# IN-17_logic_V1_0.net
KiCad netlist of a schematic drawn in EAGLE
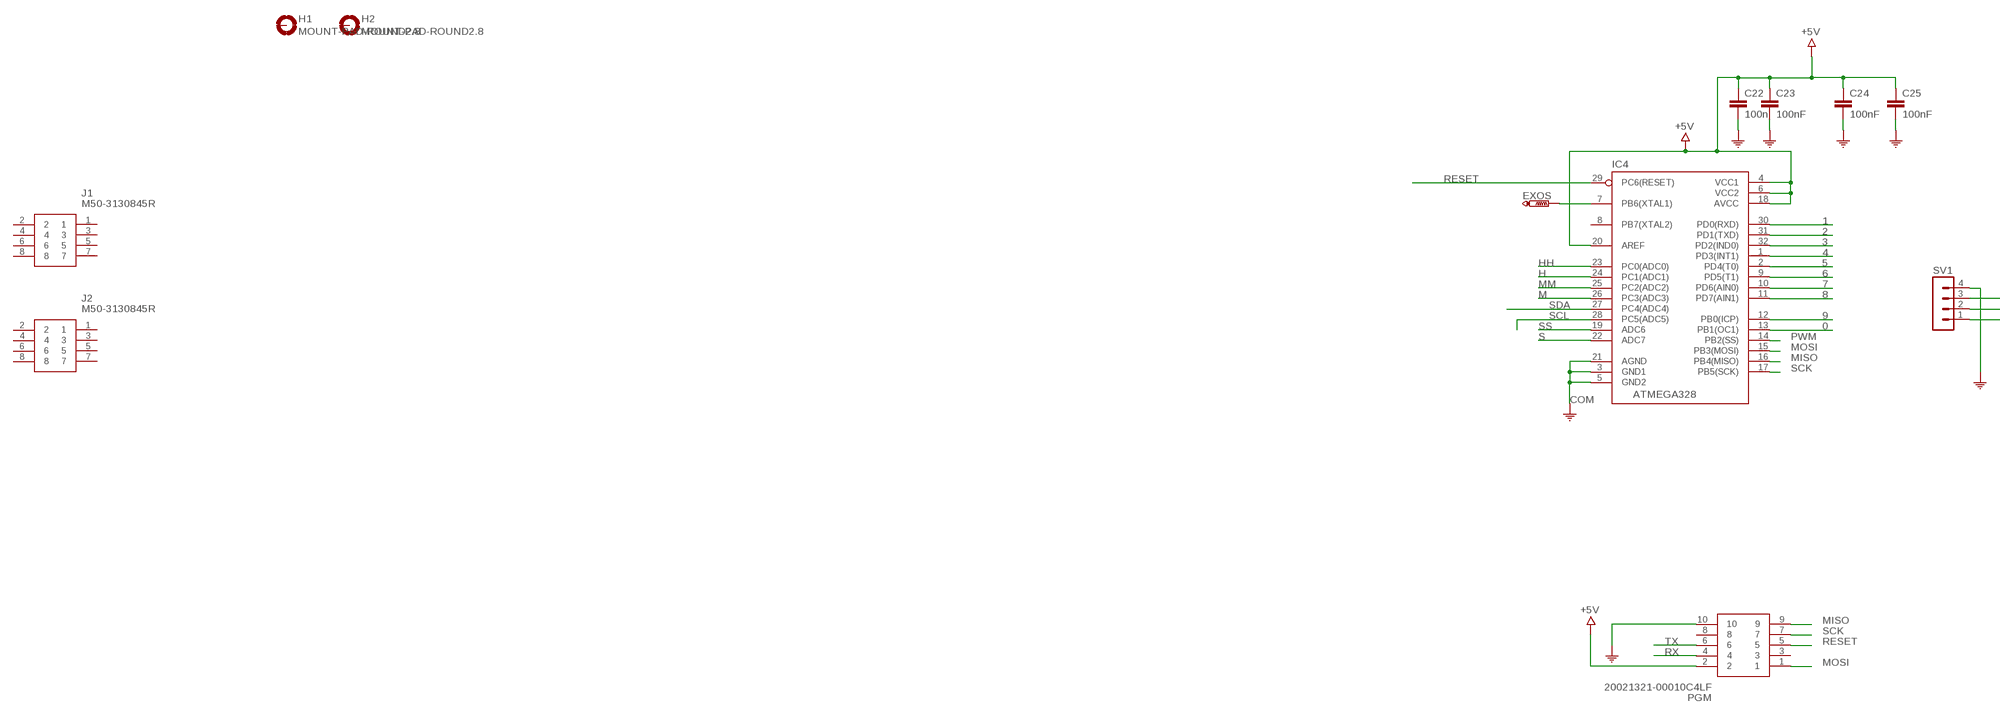
[diagram p0: schematic, sheet 1, part 1 of 2]
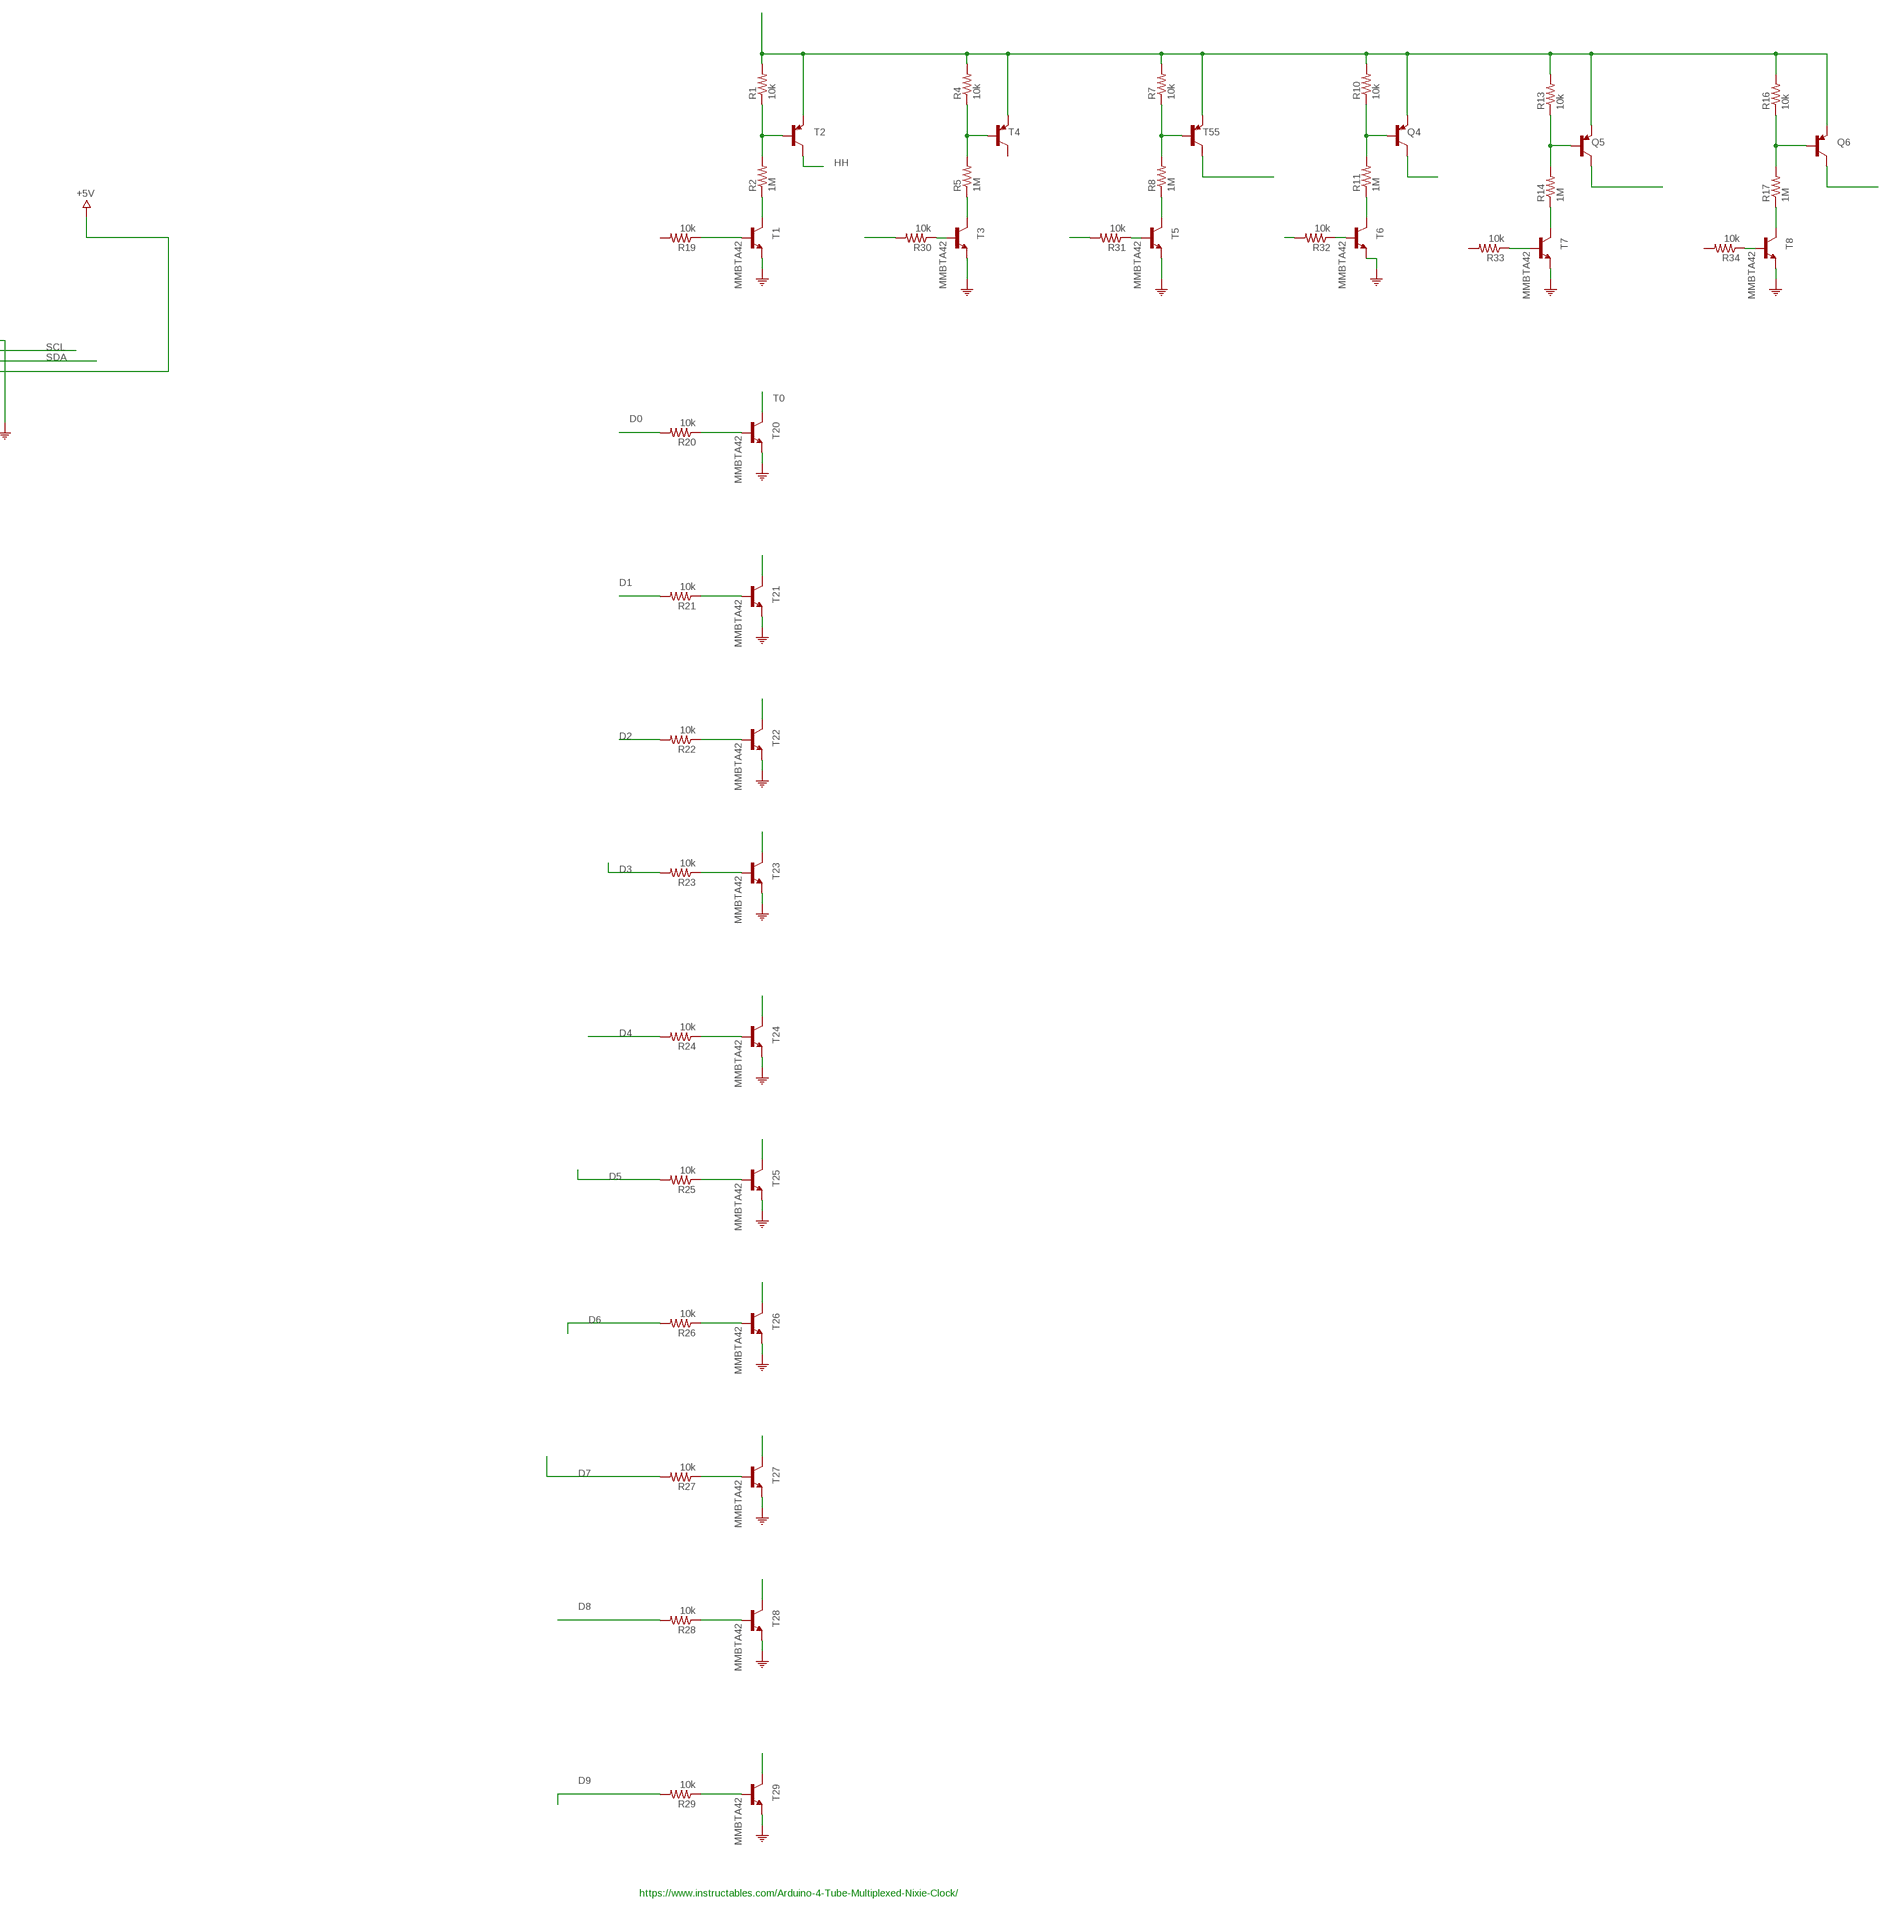
[diagram p1: schematic, sheet 1, part 2 of 2]

(export (version "E")
  (design (tool "Eeschema 10.0.6"))
  (components
    (comp (ref "C22")
      (value "100n")
      (footprint "eagle-import:C0805")
      (libsource (lib "eagle-import") (part "C-EUC0805"))
    )
    (comp (ref "C23")
      (value "100nF")
      (footprint "eagle-import:C0805")
      (libsource (lib "eagle-import") (part "C-EUC0805"))
    )
    (comp (ref "C24")
      (value "100nF")
      (footprint "eagle-import:C0805")
      (libsource (lib "eagle-import") (part "C-EUC0805"))
    )
    (comp (ref "C25")
      (value "100nF")
      (footprint "eagle-import:C0805")
      (libsource (lib "eagle-import") (part "C-EUC0805"))
    )
    (comp (ref "EXOS")
      (value "PTR1TP09R")
      (footprint "eagle-import:TP09R")
      (libsource (lib "eagle-import") (part "PTR1TP09R"))
    )
    (comp (ref "H1")
      (value "MOUNT-PAD-ROUND2.8")
      (footprint "eagle-import:2,8-PAD")
      (libsource (lib "eagle-import") (part "MOUNT-PAD-ROUND2.8"))
    )
    (comp (ref "H2")
      (value "MOUNT-PAD-ROUND2.8")
      (footprint "eagle-import:2,8-PAD")
      (libsource (lib "eagle-import") (part "MOUNT-PAD-ROUND2.8"))
    )
    (comp (ref "IC4")
      (value "ATMEGA328")
      (footprint "eagle-import:QFP032")
      (libsource (lib "eagle-import") (part "ATMEGA168-20AU"))
    )
    (comp (ref "J1")
      (value "M50-3130845R")
      (footprint "eagle-import:M503130845R")
      (fields (field (name "MOUSER_PART_NUMBER") "855-M50-3130845R"))
      (libsource (lib "eagle-import") (part "M50-3130845R"))
    )
    (comp (ref "J2")
      (value "M50-3130845R")
      (footprint "eagle-import:M503130845R")
      (fields (field (name "MOUSER_PART_NUMBER") "855-M50-3130845R"))
      (libsource (lib "eagle-import") (part "M50-3130845R"))
    )
    (comp (ref "PGM")
      (value "20021321-00010C4LF")
      (footprint "eagle-import:2002132100010C4LF")
      (fields (field (name "MOUSER_PART_NUMBER") "649-202132100010C4LF"))
      (libsource (lib "eagle-import") (part "20021321-00010C4LF"))
    )
    (comp (ref "Q4")
      (value "TRANSISTOR_BJT_PNP-SOT-23-BCE")
      (footprint "eagle-import:SOT-23")
      (libsource (lib "eagle-import") (part "TRANSISTOR_BJT_PNP-SOT-23-BCE"))
    )
    (comp (ref "Q5")
      (value "TRANSISTOR_BJT_PNP-SOT-23-BCE")
      (footprint "eagle-import:SOT-23")
      (libsource (lib "eagle-import") (part "TRANSISTOR_BJT_PNP-SOT-23-BCE"))
    )
    (comp (ref "Q6")
      (value "TRANSISTOR_BJT_PNP-SOT-23-BCE")
      (footprint "eagle-import:SOT-23")
      (libsource (lib "eagle-import") (part "TRANSISTOR_BJT_PNP-SOT-23-BCE"))
    )
    (comp (ref "R1")
      (value "10k")
      (footprint "eagle-import:R0805")
      (libsource (lib "eagle-import") (part "R-US_R0805"))
    )
    (comp (ref "R2")
      (value "1M")
      (footprint "eagle-import:R0805")
      (libsource (lib "eagle-import") (part "R-US_R0805"))
    )
    (comp (ref "R4")
      (value "10k")
      (footprint "eagle-import:R0805")
      (libsource (lib "eagle-import") (part "R-US_R0805"))
    )
    (comp (ref "R5")
      (value "1M")
      (footprint "eagle-import:R0805")
      (libsource (lib "eagle-import") (part "R-US_R0805"))
    )
    (comp (ref "R7")
      (value "10k")
      (footprint "eagle-import:R0805")
      (libsource (lib "eagle-import") (part "R-US_R0805"))
    )
    (comp (ref "R8")
      (value "1M")
      (footprint "eagle-import:R0805")
      (libsource (lib "eagle-import") (part "R-US_R0805"))
    )
    (comp (ref "R10")
      (value "10k")
      (footprint "eagle-import:R0805")
      (libsource (lib "eagle-import") (part "R-US_R0805"))
    )
    (comp (ref "R11")
      (value "1M")
      (footprint "eagle-import:R0805")
      (libsource (lib "eagle-import") (part "R-US_R0805"))
    )
    (comp (ref "R13")
      (value "10k")
      (footprint "eagle-import:R0805")
      (libsource (lib "eagle-import") (part "R-US_R0805"))
    )
    (comp (ref "R14")
      (value "1M")
      (footprint "eagle-import:R0805")
      (libsource (lib "eagle-import") (part "R-US_R0805"))
    )
    (comp (ref "R16")
      (value "10k")
      (footprint "eagle-import:R0805")
      (libsource (lib "eagle-import") (part "R-US_R0805"))
    )
    (comp (ref "R17")
      (value "1M")
      (footprint "eagle-import:R0805")
      (libsource (lib "eagle-import") (part "R-US_R0805"))
    )
    (comp (ref "R19")
      (value "10k")
      (footprint "eagle-import:R0805")
      (libsource (lib "eagle-import") (part "R-US_R0805"))
    )
    (comp (ref "R20")
      (value "10k")
      (footprint "eagle-import:R0805")
      (libsource (lib "eagle-import") (part "R-US_R0805"))
    )
    (comp (ref "R21")
      (value "10k")
      (footprint "eagle-import:R0805")
      (libsource (lib "eagle-import") (part "R-US_R0805"))
    )
    (comp (ref "R22")
      (value "10k")
      (footprint "eagle-import:R0805")
      (libsource (lib "eagle-import") (part "R-US_R0805"))
    )
    (comp (ref "R23")
      (value "10k")
      (footprint "eagle-import:R0805")
      (libsource (lib "eagle-import") (part "R-US_R0805"))
    )
    (comp (ref "R24")
      (value "10k")
      (footprint "eagle-import:R0805")
      (libsource (lib "eagle-import") (part "R-US_R0805"))
    )
    (comp (ref "R25")
      (value "10k")
      (footprint "eagle-import:R0805")
      (libsource (lib "eagle-import") (part "R-US_R0805"))
    )
    (comp (ref "R26")
      (value "10k")
      (footprint "eagle-import:R0805")
      (libsource (lib "eagle-import") (part "R-US_R0805"))
    )
    (comp (ref "R27")
      (value "10k")
      (footprint "eagle-import:R0805")
      (libsource (lib "eagle-import") (part "R-US_R0805"))
    )
    (comp (ref "R28")
      (value "10k")
      (footprint "eagle-import:R0805")
      (libsource (lib "eagle-import") (part "R-US_R0805"))
    )
    (comp (ref "R29")
      (value "10k")
      (footprint "eagle-import:R0805")
      (libsource (lib "eagle-import") (part "R-US_R0805"))
    )
    (comp (ref "R30")
      (value "10k")
      (footprint "eagle-import:R0805")
      (libsource (lib "eagle-import") (part "R-US_R0805"))
    )
    (comp (ref "R31")
      (value "10k")
      (footprint "eagle-import:R0805")
      (libsource (lib "eagle-import") (part "R-US_R0805"))
    )
    (comp (ref "R32")
      (value "10k")
      (footprint "eagle-import:R0805")
      (libsource (lib "eagle-import") (part "R-US_R0805"))
    )
    (comp (ref "R33")
      (value "10k")
      (footprint "eagle-import:R0805")
      (libsource (lib "eagle-import") (part "R-US_R0805"))
    )
    (comp (ref "R34")
      (value "10k")
      (footprint "eagle-import:R0805")
      (libsource (lib "eagle-import") (part "R-US_R0805"))
    )
    (comp (ref "SV1")
      (value "MA04-1")
      (footprint "eagle-import:MA04-1")
      (libsource (lib "eagle-import") (part "MA04-1"))
    )
    (comp (ref "T1")
      (value "MMBTA42")
      (footprint "eagle-import:SOT23")
      (libsource (lib "eagle-import") (part "BC846"))
    )
    (comp (ref "T2")
      (value "TRANSISTOR_BJT_PNP-SOT-23-BCE")
      (footprint "eagle-import:SOT-23")
      (libsource (lib "eagle-import") (part "TRANSISTOR_BJT_PNP-SOT-23-BCE"))
    )
    (comp (ref "T3")
      (value "MMBTA42")
      (footprint "eagle-import:SOT23")
      (libsource (lib "eagle-import") (part "BC846"))
    )
    (comp (ref "T4")
      (value "TRANSISTOR_BJT_PNP-SOT-23-BCE")
      (footprint "eagle-import:SOT-23")
      (libsource (lib "eagle-import") (part "TRANSISTOR_BJT_PNP-SOT-23-BCE"))
    )
    (comp (ref "T5")
      (value "MMBTA42")
      (footprint "eagle-import:SOT23")
      (libsource (lib "eagle-import") (part "BC846"))
    )
    (comp (ref "T6")
      (value "MMBTA42")
      (footprint "eagle-import:SOT23")
      (libsource (lib "eagle-import") (part "BC846"))
    )
    (comp (ref "T7")
      (value "MMBTA42")
      (footprint "eagle-import:SOT23")
      (libsource (lib "eagle-import") (part "BC846"))
    )
    (comp (ref "T8")
      (value "MMBTA42")
      (footprint "eagle-import:SOT23")
      (libsource (lib "eagle-import") (part "BC846"))
    )
    (comp (ref "T20")
      (value "MMBTA42")
      (footprint "eagle-import:SOT23")
      (libsource (lib "eagle-import") (part "BC846"))
    )
    (comp (ref "T21")
      (value "MMBTA42")
      (footprint "eagle-import:SOT23")
      (libsource (lib "eagle-import") (part "BC846"))
    )
    (comp (ref "T22")
      (value "MMBTA42")
      (footprint "eagle-import:SOT23")
      (libsource (lib "eagle-import") (part "BC846"))
    )
    (comp (ref "T23")
      (value "MMBTA42")
      (footprint "eagle-import:SOT23")
      (libsource (lib "eagle-import") (part "BC846"))
    )
    (comp (ref "T24")
      (value "MMBTA42")
      (footprint "eagle-import:SOT23")
      (libsource (lib "eagle-import") (part "BC846"))
    )
    (comp (ref "T25")
      (value "MMBTA42")
      (footprint "eagle-import:SOT23")
      (libsource (lib "eagle-import") (part "BC846"))
    )
    (comp (ref "T26")
      (value "MMBTA42")
      (footprint "eagle-import:SOT23")
      (libsource (lib "eagle-import") (part "BC846"))
    )
    (comp (ref "T27")
      (value "MMBTA42")
      (footprint "eagle-import:SOT23")
      (libsource (lib "eagle-import") (part "BC846"))
    )
    (comp (ref "T28")
      (value "MMBTA42")
      (footprint "eagle-import:SOT23")
      (libsource (lib "eagle-import") (part "BC846"))
    )
    (comp (ref "T29")
      (value "MMBTA42")
      (footprint "eagle-import:SOT23")
      (libsource (lib "eagle-import") (part "BC846"))
    )
    (comp (ref "T55")
      (value "TRANSISTOR_BJT_PNP-SOT-23-BCE")
      (footprint "eagle-import:SOT-23")
      (libsource (lib "eagle-import") (part "TRANSISTOR_BJT_PNP-SOT-23-BCE"))
    )
  )
  (nets
    (net (code "1") (name "+5V") (class "Default")
      (node (ref "C22") (pin "1") (pinfunction "1_1") (pintype "passive"))
      (node (ref "C23") (pin "1") (pinfunction "1_1") (pintype "passive"))
      (node (ref "C24") (pin "1") (pinfunction "1_1") (pintype "passive"))
      (node (ref "C25") (pin "1") (pinfunction "1_1") (pintype "passive"))
      (node (ref "IC4") (pin "18") (pinfunction "AVCC_18") (pintype "passive"))
      (node (ref "IC4") (pin "20") (pinfunction "AREF_20") (pintype "passive"))
      (node (ref "IC4") (pin "4") (pinfunction "VCC1_4") (pintype "power_in"))
      (node (ref "IC4") (pin "6") (pinfunction "VCC2_6") (pintype "power_in"))
      (node (ref "PGM") (pin "2") (pinfunction "2_2") (pintype "bidirectional"))
      (node (ref "SV1") (pin "1") (pinfunction "1_1") (pintype "passive"))
    )
    (net (code "2") (name "/0") (class "Default")
      (node (ref "IC4") (pin "13") (pinfunction "PB1(OC1)_13") (pintype "bidirectional"))
    )
    (net (code "3") (name "/1") (class "Default")
      (node (ref "IC4") (pin "30") (pinfunction "PD0(RXD)_30") (pintype "bidirectional"))
    )
    (net (code "4") (name "/2") (class "Default")
      (node (ref "IC4") (pin "31") (pinfunction "PD1(TXD)_31") (pintype "bidirectional"))
    )
    (net (code "5") (name "/3") (class "Default")
      (node (ref "IC4") (pin "32") (pinfunction "PD2(IND0)_32") (pintype "bidirectional"))
    )
    (net (code "6") (name "/4") (class "Default")
      (node (ref "IC4") (pin "1") (pinfunction "PD3(INT1)_1") (pintype "bidirectional"))
    )
    (net (code "7") (name "/5") (class "Default")
      (node (ref "IC4") (pin "2") (pinfunction "PD4(T0)_2") (pintype "bidirectional"))
    )
    (net (code "8") (name "/6") (class "Default")
      (node (ref "IC4") (pin "9") (pinfunction "PD5(T1)_9") (pintype "bidirectional"))
    )
    (net (code "9") (name "/7") (class "Default")
      (node (ref "IC4") (pin "10") (pinfunction "PD6(AIN0)_10") (pintype "bidirectional"))
    )
    (net (code "10") (name "/8") (class "Default")
      (node (ref "IC4") (pin "11") (pinfunction "PD7(AIN1)_11") (pintype "bidirectional"))
    )
    (net (code "11") (name "/9") (class "Default")
      (node (ref "IC4") (pin "12") (pinfunction "PB0(ICP)_12") (pintype "bidirectional"))
    )
    (net (code "12") (name "/D0") (class "Default")
      (node (ref "R20") (pin "2") (pinfunction "2_2") (pintype "passive"))
    )
    (net (code "13") (name "/D1") (class "Default")
      (node (ref "R21") (pin "2") (pinfunction "2_2") (pintype "passive"))
    )
    (net (code "14") (name "/D2") (class "Default")
      (node (ref "R22") (pin "2") (pinfunction "2_2") (pintype "passive"))
    )
    (net (code "15") (name "/D3") (class "Default")
      (node (ref "R23") (pin "2") (pinfunction "2_2") (pintype "passive"))
    )
    (net (code "16") (name "/D4") (class "Default")
      (node (ref "R24") (pin "2") (pinfunction "2_2") (pintype "passive"))
    )
    (net (code "17") (name "/D5") (class "Default")
      (node (ref "R25") (pin "2") (pinfunction "2_2") (pintype "passive"))
    )
    (net (code "18") (name "/D6") (class "Default")
      (node (ref "R26") (pin "2") (pinfunction "2_2") (pintype "passive"))
    )
    (net (code "19") (name "/D7") (class "Default")
      (node (ref "R27") (pin "2") (pinfunction "2_2") (pintype "passive"))
    )
    (net (code "20") (name "/D8") (class "Default")
      (node (ref "R28") (pin "2") (pinfunction "2_2") (pintype "passive"))
    )
    (net (code "21") (name "/D9") (class "Default")
      (node (ref "R29") (pin "2") (pinfunction "2_2") (pintype "passive"))
    )
    (net (code "22") (name "/H") (class "Default")
      (node (ref "IC4") (pin "24") (pinfunction "PC1(ADC1)_24") (pintype "passive"))
    )
    (net (code "23") (name "/HH") (class "Default")
      (node (ref "IC4") (pin "23") (pinfunction "PC0(ADC0)_23") (pintype "passive"))
      (node (ref "T2") (pin "2") (pinfunction "C_2") (pintype "passive"))
    )
    (net (code "24") (name "/M") (class "Default")
      (node (ref "IC4") (pin "26") (pinfunction "PC3(ADC3)_26") (pintype "passive"))
    )
    (net (code "25") (name "/MISO") (class "Default")
      (node (ref "IC4") (pin "16") (pinfunction "PB4(MISO)_16") (pintype "bidirectional"))
      (node (ref "PGM") (pin "9") (pinfunction "9_9") (pintype "bidirectional"))
    )
    (net (code "26") (name "/MM") (class "Default")
      (node (ref "IC4") (pin "25") (pinfunction "PC2(ADC2)_25") (pintype "passive"))
    )
    (net (code "27") (name "/MOSI") (class "Default")
      (node (ref "IC4") (pin "15") (pinfunction "PB3(MOSI)_15") (pintype "bidirectional"))
      (node (ref "PGM") (pin "1") (pinfunction "1_1") (pintype "bidirectional"))
    )
    (net (code "28") (name "/PWM") (class "Default")
      (node (ref "IC4") (pin "14") (pinfunction "PB2(SS)_14") (pintype "bidirectional"))
    )
    (net (code "29") (name "/RESET") (class "Default")
      (node (ref "IC4") (pin "29") (pinfunction "PC6(RESET)_29") (pintype "bidirectional"))
      (node (ref "PGM") (pin "5") (pinfunction "5_5") (pintype "bidirectional"))
    )
    (net (code "30") (name "/RX") (class "Default")
      (node (ref "PGM") (pin "4") (pinfunction "4_4") (pintype "bidirectional"))
    )
    (net (code "31") (name "/S") (class "Default")
      (node (ref "IC4") (pin "22") (pinfunction "ADC7_22") (pintype "passive"))
    )
    (net (code "32") (name "/SCK") (class "Default")
      (node (ref "IC4") (pin "17") (pinfunction "PB5(SCK)_17") (pintype "bidirectional"))
      (node (ref "PGM") (pin "7") (pinfunction "7_7") (pintype "bidirectional"))
    )
    (net (code "33") (name "/SCL") (class "Default")
      (node (ref "IC4") (pin "28") (pinfunction "PC5(ADC5)_28") (pintype "passive"))
      (node (ref "SV1") (pin "3") (pinfunction "3_3") (pintype "passive"))
    )
    (net (code "34") (name "/SDA") (class "Default")
      (node (ref "IC4") (pin "27") (pinfunction "PC4(ADC4)_27") (pintype "passive"))
      (node (ref "SV1") (pin "2") (pinfunction "2_2") (pintype "passive"))
    )
    (net (code "35") (name "/SS") (class "Default")
      (node (ref "IC4") (pin "19") (pinfunction "ADC6_19") (pintype "passive"))
    )
    (net (code "36") (name "/T0") (class "Default")
      (node (ref "T20") (pin "3") (pinfunction "C_3") (pintype "passive"))
    )
    (net (code "37") (name "/TX") (class "Default")
      (node (ref "PGM") (pin "6") (pinfunction "6_6") (pintype "bidirectional"))
    )
    (net (code "38") (name "COM") (class "Default")
      (node (ref "C22") (pin "2") (pinfunction "2_2") (pintype "passive"))
      (node (ref "C23") (pin "2") (pinfunction "2_2") (pintype "passive"))
      (node (ref "C24") (pin "2") (pinfunction "2_2") (pintype "passive"))
      (node (ref "C25") (pin "2") (pinfunction "2_2") (pintype "passive"))
      (node (ref "IC4") (pin "21") (pinfunction "AGND_21") (pintype "passive"))
      (node (ref "IC4") (pin "3") (pinfunction "GND1_3") (pintype "power_in"))
      (node (ref "IC4") (pin "5") (pinfunction "GND2_5") (pintype "power_in"))
      (node (ref "PGM") (pin "10") (pinfunction "10_10") (pintype "bidirectional"))
      (node (ref "SV1") (pin "4") (pinfunction "4_4") (pintype "passive"))
      (node (ref "T1") (pin "2") (pinfunction "E_2") (pintype "passive"))
      (node (ref "T20") (pin "2") (pinfunction "E_2") (pintype "passive"))
      (node (ref "T21") (pin "2") (pinfunction "E_2") (pintype "passive"))
      (node (ref "T22") (pin "2") (pinfunction "E_2") (pintype "passive"))
      (node (ref "T23") (pin "2") (pinfunction "E_2") (pintype "passive"))
      (node (ref "T24") (pin "2") (pinfunction "E_2") (pintype "passive"))
      (node (ref "T25") (pin "2") (pinfunction "E_2") (pintype "passive"))
      (node (ref "T26") (pin "2") (pinfunction "E_2") (pintype "passive"))
      (node (ref "T27") (pin "2") (pinfunction "E_2") (pintype "passive"))
      (node (ref "T28") (pin "2") (pinfunction "E_2") (pintype "passive"))
      (node (ref "T29") (pin "2") (pinfunction "E_2") (pintype "passive"))
      (node (ref "T3") (pin "2") (pinfunction "E_2") (pintype "passive"))
      (node (ref "T5") (pin "2") (pinfunction "E_2") (pintype "passive"))
      (node (ref "T6") (pin "2") (pinfunction "E_2") (pintype "passive"))
      (node (ref "T7") (pin "2") (pinfunction "E_2") (pintype "passive"))
      (node (ref "T8") (pin "2") (pinfunction "E_2") (pintype "passive"))
    )
    (net (code "39") (name "Net-(IC4-PB6(XTAL1))") (class "Default")
      (node (ref "EXOS") (pin "TP") (pinfunction "TP_TP") (pintype "input"))
      (node (ref "IC4") (pin "7") (pinfunction "PB6(XTAL1)_7") (pintype "passive"))
    )
    (net (code "40") (name "Net-(Q4-B)") (class "Default")
      (node (ref "Q4") (pin "1") (pinfunction "B_1") (pintype "passive"))
      (node (ref "R10") (pin "1") (pinfunction "1_1") (pintype "passive"))
      (node (ref "R11") (pin "2") (pinfunction "2_2") (pintype "passive"))
    )
    (net (code "41") (name "Net-(Q4-E)") (class "Default")
      (node (ref "Q4") (pin "3") (pinfunction "E_3") (pintype "passive"))
      (node (ref "Q5") (pin "3") (pinfunction "E_3") (pintype "passive"))
      (node (ref "Q6") (pin "3") (pinfunction "E_3") (pintype "passive"))
      (node (ref "R1") (pin "2") (pinfunction "2_2") (pintype "passive"))
      (node (ref "R10") (pin "2") (pinfunction "2_2") (pintype "passive"))
      (node (ref "R13") (pin "2") (pinfunction "2_2") (pintype "passive"))
      (node (ref "R16") (pin "2") (pinfunction "2_2") (pintype "passive"))
      (node (ref "R4") (pin "2") (pinfunction "2_2") (pintype "passive"))
      (node (ref "R7") (pin "2") (pinfunction "2_2") (pintype "passive"))
      (node (ref "T2") (pin "3") (pinfunction "E_3") (pintype "passive"))
      (node (ref "T4") (pin "3") (pinfunction "E_3") (pintype "passive"))
      (node (ref "T55") (pin "3") (pinfunction "E_3") (pintype "passive"))
    )
    (net (code "42") (name "Net-(Q5-B)") (class "Default")
      (node (ref "Q5") (pin "1") (pinfunction "B_1") (pintype "passive"))
      (node (ref "R13") (pin "1") (pinfunction "1_1") (pintype "passive"))
      (node (ref "R14") (pin "2") (pinfunction "2_2") (pintype "passive"))
    )
    (net (code "43") (name "Net-(Q6-B)") (class "Default")
      (node (ref "Q6") (pin "1") (pinfunction "B_1") (pintype "passive"))
      (node (ref "R16") (pin "1") (pinfunction "1_1") (pintype "passive"))
      (node (ref "R17") (pin "2") (pinfunction "2_2") (pintype "passive"))
    )
    (net (code "44") (name "Net-(T1-B)") (class "Default")
      (node (ref "R19") (pin "1") (pinfunction "1_1") (pintype "passive"))
      (node (ref "T1") (pin "1") (pinfunction "B_1") (pintype "passive"))
    )
    (net (code "45") (name "Net-(T1-C)") (class "Default")
      (node (ref "R2") (pin "1") (pinfunction "1_1") (pintype "passive"))
      (node (ref "T1") (pin "3") (pinfunction "C_3") (pintype "passive"))
    )
    (net (code "46") (name "Net-(T2-B)") (class "Default")
      (node (ref "R1") (pin "1") (pinfunction "1_1") (pintype "passive"))
      (node (ref "R2") (pin "2") (pinfunction "2_2") (pintype "passive"))
      (node (ref "T2") (pin "1") (pinfunction "B_1") (pintype "passive"))
    )
    (net (code "47") (name "Net-(T3-B)") (class "Default")
      (node (ref "R30") (pin "1") (pinfunction "1_1") (pintype "passive"))
      (node (ref "T3") (pin "1") (pinfunction "B_1") (pintype "passive"))
    )
    (net (code "48") (name "Net-(T3-C)") (class "Default")
      (node (ref "R5") (pin "1") (pinfunction "1_1") (pintype "passive"))
      (node (ref "T3") (pin "3") (pinfunction "C_3") (pintype "passive"))
    )
    (net (code "49") (name "Net-(T4-B)") (class "Default")
      (node (ref "R4") (pin "1") (pinfunction "1_1") (pintype "passive"))
      (node (ref "R5") (pin "2") (pinfunction "2_2") (pintype "passive"))
      (node (ref "T4") (pin "1") (pinfunction "B_1") (pintype "passive"))
    )
    (net (code "50") (name "Net-(T5-B)") (class "Default")
      (node (ref "R31") (pin "1") (pinfunction "1_1") (pintype "passive"))
      (node (ref "T5") (pin "1") (pinfunction "B_1") (pintype "passive"))
    )
    (net (code "51") (name "Net-(T5-C)") (class "Default")
      (node (ref "R8") (pin "1") (pinfunction "1_1") (pintype "passive"))
      (node (ref "T5") (pin "3") (pinfunction "C_3") (pintype "passive"))
    )
    (net (code "52") (name "Net-(T6-B)") (class "Default")
      (node (ref "R32") (pin "1") (pinfunction "1_1") (pintype "passive"))
      (node (ref "T6") (pin "1") (pinfunction "B_1") (pintype "passive"))
    )
    (net (code "53") (name "Net-(T6-C)") (class "Default")
      (node (ref "R11") (pin "1") (pinfunction "1_1") (pintype "passive"))
      (node (ref "T6") (pin "3") (pinfunction "C_3") (pintype "passive"))
    )
    (net (code "54") (name "Net-(T7-B)") (class "Default")
      (node (ref "R33") (pin "1") (pinfunction "1_1") (pintype "passive"))
      (node (ref "T7") (pin "1") (pinfunction "B_1") (pintype "passive"))
    )
    (net (code "55") (name "Net-(T7-C)") (class "Default")
      (node (ref "R14") (pin "1") (pinfunction "1_1") (pintype "passive"))
      (node (ref "T7") (pin "3") (pinfunction "C_3") (pintype "passive"))
    )
    (net (code "56") (name "Net-(T8-B)") (class "Default")
      (node (ref "R34") (pin "1") (pinfunction "1_1") (pintype "passive"))
      (node (ref "T8") (pin "1") (pinfunction "B_1") (pintype "passive"))
    )
    (net (code "57") (name "Net-(T8-C)") (class "Default")
      (node (ref "R17") (pin "1") (pinfunction "1_1") (pintype "passive"))
      (node (ref "T8") (pin "3") (pinfunction "C_3") (pintype "passive"))
    )
    (net (code "58") (name "Net-(T20-B)") (class "Default")
      (node (ref "R20") (pin "1") (pinfunction "1_1") (pintype "passive"))
      (node (ref "T20") (pin "1") (pinfunction "B_1") (pintype "passive"))
    )
    (net (code "59") (name "Net-(T21-B)") (class "Default")
      (node (ref "R21") (pin "1") (pinfunction "1_1") (pintype "passive"))
      (node (ref "T21") (pin "1") (pinfunction "B_1") (pintype "passive"))
    )
    (net (code "60") (name "Net-(T22-B)") (class "Default")
      (node (ref "R22") (pin "1") (pinfunction "1_1") (pintype "passive"))
      (node (ref "T22") (pin "1") (pinfunction "B_1") (pintype "passive"))
    )
    (net (code "61") (name "Net-(T23-B)") (class "Default")
      (node (ref "R23") (pin "1") (pinfunction "1_1") (pintype "passive"))
      (node (ref "T23") (pin "1") (pinfunction "B_1") (pintype "passive"))
    )
    (net (code "62") (name "Net-(T24-B)") (class "Default")
      (node (ref "R24") (pin "1") (pinfunction "1_1") (pintype "passive"))
      (node (ref "T24") (pin "1") (pinfunction "B_1") (pintype "passive"))
    )
    (net (code "63") (name "Net-(T25-B)") (class "Default")
      (node (ref "R25") (pin "1") (pinfunction "1_1") (pintype "passive"))
      (node (ref "T25") (pin "1") (pinfunction "B_1") (pintype "passive"))
    )
    (net (code "64") (name "Net-(T26-B)") (class "Default")
      (node (ref "R26") (pin "1") (pinfunction "1_1") (pintype "passive"))
      (node (ref "T26") (pin "1") (pinfunction "B_1") (pintype "passive"))
    )
    (net (code "65") (name "Net-(T27-B)") (class "Default")
      (node (ref "R27") (pin "1") (pinfunction "1_1") (pintype "passive"))
      (node (ref "T27") (pin "1") (pinfunction "B_1") (pintype "passive"))
    )
    (net (code "66") (name "Net-(T28-B)") (class "Default")
      (node (ref "R28") (pin "1") (pinfunction "1_1") (pintype "passive"))
      (node (ref "T28") (pin "1") (pinfunction "B_1") (pintype "passive"))
    )
    (net (code "67") (name "Net-(T29-B)") (class "Default")
      (node (ref "R29") (pin "1") (pinfunction "1_1") (pintype "passive"))
      (node (ref "T29") (pin "1") (pinfunction "B_1") (pintype "passive"))
    )
    (net (code "68") (name "Net-(T55-B)") (class "Default")
      (node (ref "R7") (pin "1") (pinfunction "1_1") (pintype "passive"))
      (node (ref "R8") (pin "2") (pinfunction "2_2") (pintype "passive"))
      (node (ref "T55") (pin "1") (pinfunction "B_1") (pintype "passive"))
    )
    (net (code "69") (name "unconnected-(H1-MOUNT-PadB2,8)") (class "Default")
      (node (ref "H1") (pin "B2,8") (pinfunction "MOUNT_B2,8") (pintype "passive"))
    )
    (net (code "70") (name "unconnected-(H2-MOUNT-PadB2,8)") (class "Default")
      (node (ref "H2") (pin "B2,8") (pinfunction "MOUNT_B2,8") (pintype "passive"))
    )
    (net (code "71") (name "unconnected-(IC4-PB7(XTAL2)-Pad8)") (class "Default")
      (node (ref "IC4") (pin "8") (pinfunction "PB7(XTAL2)_8") (pintype "passive"))
    )
    (net (code "72") (name "unconnected-(J1-Pad1)") (class "Default")
      (node (ref "J1") (pin "1") (pinfunction "1_1") (pintype "bidirectional"))
    )
    (net (code "73") (name "unconnected-(J1-Pad2)") (class "Default")
      (node (ref "J1") (pin "2") (pinfunction "2_2") (pintype "bidirectional"))
    )
    (net (code "74") (name "unconnected-(J1-Pad3)") (class "Default")
      (node (ref "J1") (pin "3") (pinfunction "3_3") (pintype "bidirectional"))
    )
    (net (code "75") (name "unconnected-(J1-Pad4)") (class "Default")
      (node (ref "J1") (pin "4") (pinfunction "4_4") (pintype "bidirectional"))
    )
    (net (code "76") (name "unconnected-(J1-Pad5)") (class "Default")
      (node (ref "J1") (pin "5") (pinfunction "5_5") (pintype "bidirectional"))
    )
    (net (code "77") (name "unconnected-(J1-Pad6)") (class "Default")
      (node (ref "J1") (pin "6") (pinfunction "6_6") (pintype "bidirectional"))
    )
    (net (code "78") (name "unconnected-(J1-Pad7)") (class "Default")
      (node (ref "J1") (pin "7") (pinfunction "7_7") (pintype "bidirectional"))
    )
    (net (code "79") (name "unconnected-(J1-Pad8)") (class "Default")
      (node (ref "J1") (pin "8") (pinfunction "8_8") (pintype "bidirectional"))
    )
    (net (code "80") (name "unconnected-(J2-Pad1)") (class "Default")
      (node (ref "J2") (pin "1") (pinfunction "1_1") (pintype "bidirectional"))
    )
    (net (code "81") (name "unconnected-(J2-Pad2)") (class "Default")
      (node (ref "J2") (pin "2") (pinfunction "2_2") (pintype "bidirectional"))
    )
    (net (code "82") (name "unconnected-(J2-Pad3)") (class "Default")
      (node (ref "J2") (pin "3") (pinfunction "3_3") (pintype "bidirectional"))
    )
    (net (code "83") (name "unconnected-(J2-Pad4)") (class "Default")
      (node (ref "J2") (pin "4") (pinfunction "4_4") (pintype "bidirectional"))
    )
    (net (code "84") (name "unconnected-(J2-Pad5)") (class "Default")
      (node (ref "J2") (pin "5") (pinfunction "5_5") (pintype "bidirectional"))
    )
    (net (code "85") (name "unconnected-(J2-Pad6)") (class "Default")
      (node (ref "J2") (pin "6") (pinfunction "6_6") (pintype "bidirectional"))
    )
    (net (code "86") (name "unconnected-(J2-Pad7)") (class "Default")
      (node (ref "J2") (pin "7") (pinfunction "7_7") (pintype "bidirectional"))
    )
    (net (code "87") (name "unconnected-(J2-Pad8)") (class "Default")
      (node (ref "J2") (pin "8") (pinfunction "8_8") (pintype "bidirectional"))
    )
    (net (code "88") (name "unconnected-(PGM-Pad3)") (class "Default")
      (node (ref "PGM") (pin "3") (pinfunction "3_3") (pintype "bidirectional"))
    )
    (net (code "89") (name "unconnected-(PGM-Pad8)") (class "Default")
      (node (ref "PGM") (pin "8") (pinfunction "8_8") (pintype "bidirectional"))
    )
    (net (code "90") (name "unconnected-(Q4-C-Pad2)") (class "Default")
      (node (ref "Q4") (pin "2") (pinfunction "C_2") (pintype "passive"))
    )
    (net (code "91") (name "unconnected-(Q5-C-Pad2)") (class "Default")
      (node (ref "Q5") (pin "2") (pinfunction "C_2") (pintype "passive"))
    )
    (net (code "92") (name "unconnected-(Q6-C-Pad2)") (class "Default")
      (node (ref "Q6") (pin "2") (pinfunction "C_2") (pintype "passive"))
    )
    (net (code "93") (name "unconnected-(R19-Pad2)") (class "Default")
      (node (ref "R19") (pin "2") (pinfunction "2_2") (pintype "passive"))
    )
    (net (code "94") (name "unconnected-(R30-Pad2)") (class "Default")
      (node (ref "R30") (pin "2") (pinfunction "2_2") (pintype "passive"))
    )
    (net (code "95") (name "unconnected-(R31-Pad2)") (class "Default")
      (node (ref "R31") (pin "2") (pinfunction "2_2") (pintype "passive"))
    )
    (net (code "96") (name "unconnected-(R32-Pad2)") (class "Default")
      (node (ref "R32") (pin "2") (pinfunction "2_2") (pintype "passive"))
    )
    (net (code "97") (name "unconnected-(R33-Pad2)") (class "Default")
      (node (ref "R33") (pin "2") (pinfunction "2_2") (pintype "passive"))
    )
    (net (code "98") (name "unconnected-(R34-Pad2)") (class "Default")
      (node (ref "R34") (pin "2") (pinfunction "2_2") (pintype "passive"))
    )
    (net (code "99") (name "unconnected-(T4-C-Pad2)") (class "Default")
      (node (ref "T4") (pin "2") (pinfunction "C_2") (pintype "passive"))
    )
    (net (code "100") (name "unconnected-(T21-C-Pad3)") (class "Default")
      (node (ref "T21") (pin "3") (pinfunction "C_3") (pintype "passive"))
    )
    (net (code "101") (name "unconnected-(T22-C-Pad3)") (class "Default")
      (node (ref "T22") (pin "3") (pinfunction "C_3") (pintype "passive"))
    )
    (net (code "102") (name "unconnected-(T23-C-Pad3)") (class "Default")
      (node (ref "T23") (pin "3") (pinfunction "C_3") (pintype "passive"))
    )
    (net (code "103") (name "unconnected-(T24-C-Pad3)") (class "Default")
      (node (ref "T24") (pin "3") (pinfunction "C_3") (pintype "passive"))
    )
    (net (code "104") (name "unconnected-(T25-C-Pad3)") (class "Default")
      (node (ref "T25") (pin "3") (pinfunction "C_3") (pintype "passive"))
    )
    (net (code "105") (name "unconnected-(T26-C-Pad3)") (class "Default")
      (node (ref "T26") (pin "3") (pinfunction "C_3") (pintype "passive"))
    )
    (net (code "106") (name "unconnected-(T27-C-Pad3)") (class "Default")
      (node (ref "T27") (pin "3") (pinfunction "C_3") (pintype "passive"))
    )
    (net (code "107") (name "unconnected-(T28-C-Pad3)") (class "Default")
      (node (ref "T28") (pin "3") (pinfunction "C_3") (pintype "passive"))
    )
    (net (code "108") (name "unconnected-(T29-C-Pad3)") (class "Default")
      (node (ref "T29") (pin "3") (pinfunction "C_3") (pintype "passive"))
    )
    (net (code "109") (name "unconnected-(T55-C-Pad2)") (class "Default")
      (node (ref "T55") (pin "2") (pinfunction "C_2") (pintype "passive"))
    )
  )
)
